# RHD2132_HS-accel-JAE.net
KiCad netlist of a schematic drawn in EAGLE
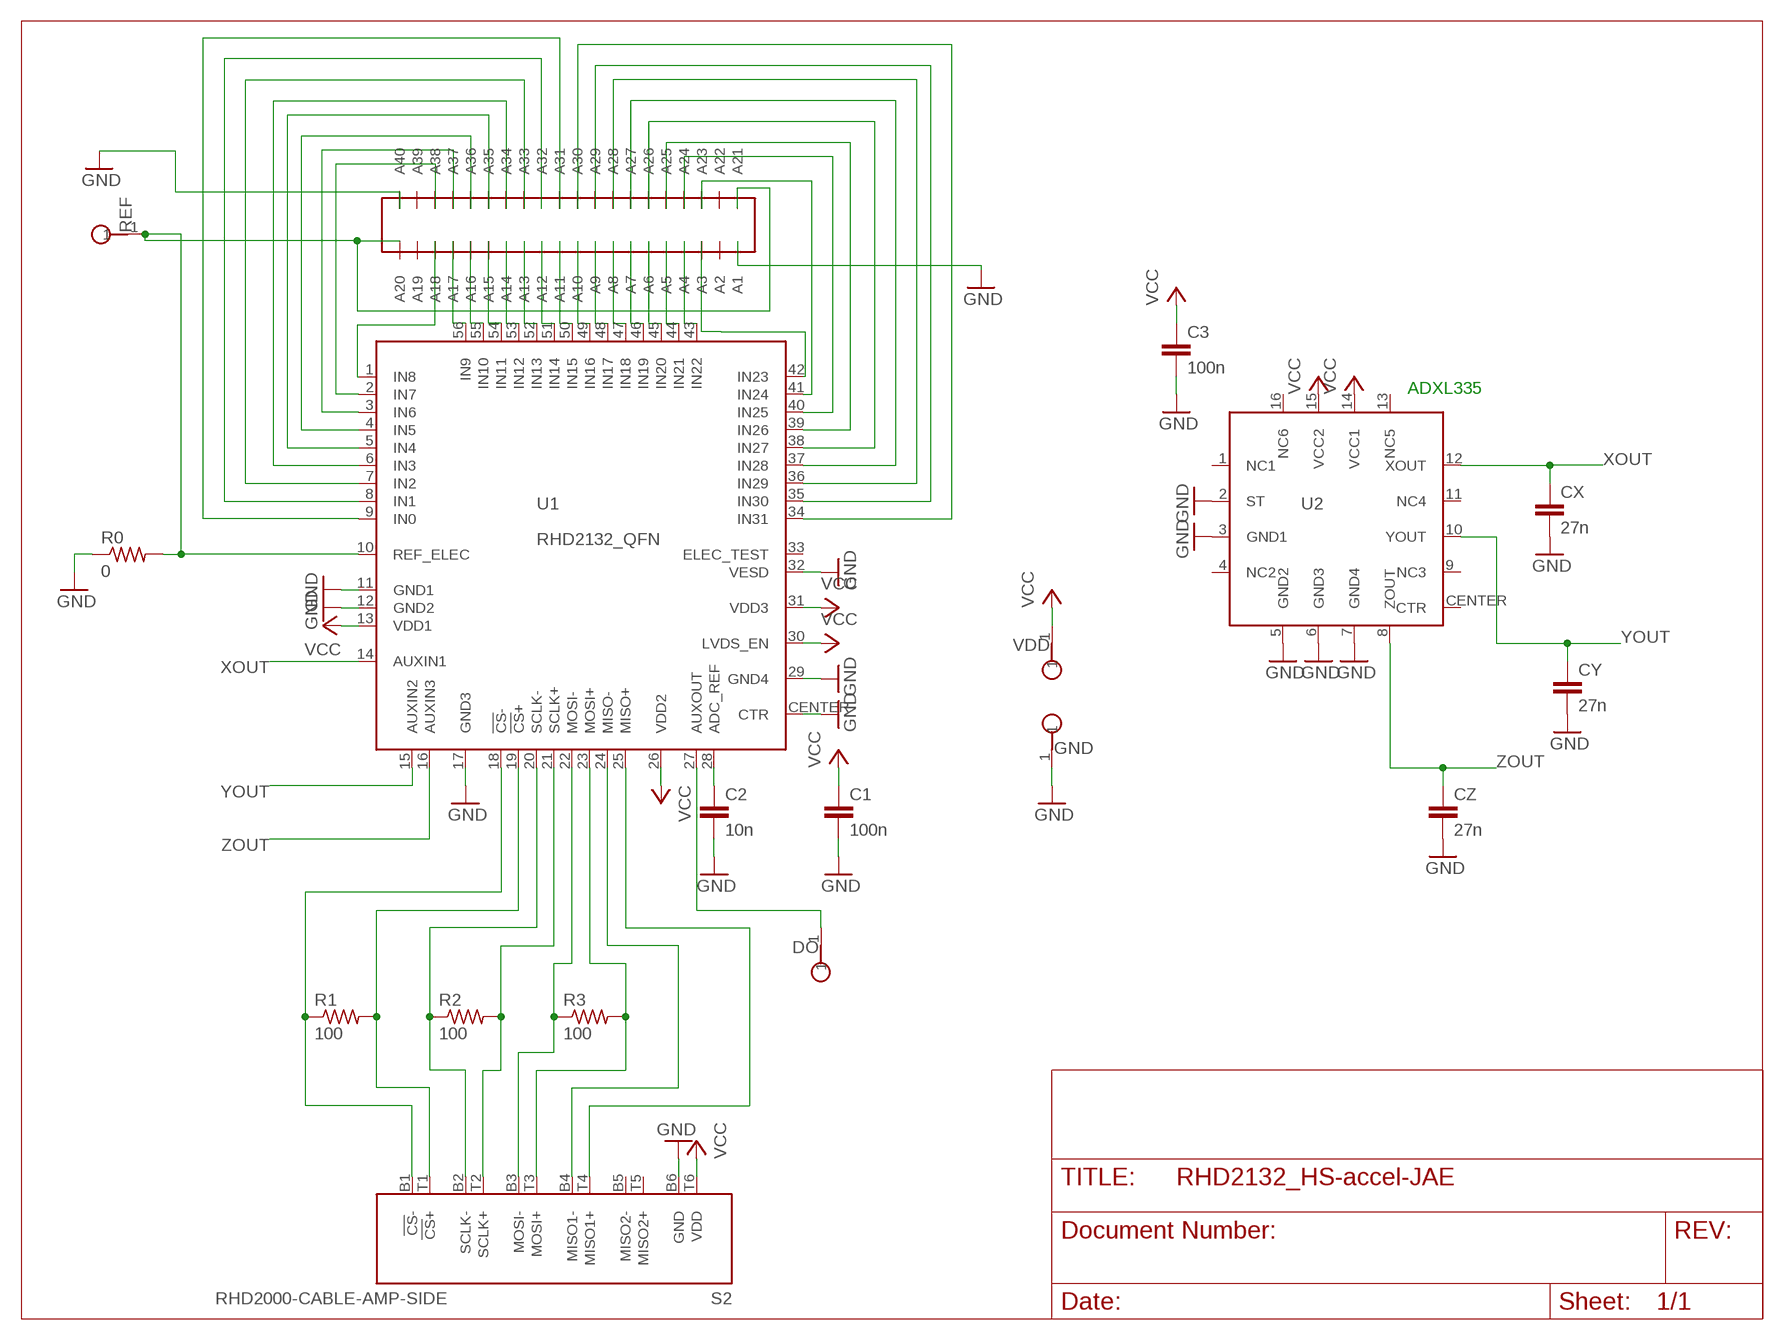
[diagram p0: schematic, sheet 1]

(export (version "E")
  (design (tool "Eeschema 10.0.6"))
  (components
    (comp (ref "C1")
      (value "100n")
      (footprint "eagle-import:0402")
      (libsource (lib "eagle-import") (part "C_0402"))
    )
    (comp (ref "C2")
      (value "10n")
      (footprint "eagle-import:0402")
      (libsource (lib "eagle-import") (part "C_0402"))
    )
    (comp (ref "C3")
      (value "100n")
      (footprint "eagle-import:0402")
      (libsource (lib "eagle-import") (part "C_0402"))
    )
    (comp (ref "CX")
      (value "27n")
      (footprint "eagle-import:0402")
      (libsource (lib "eagle-import") (part "C_0402"))
    )
    (comp (ref "CY")
      (value "27n")
      (footprint "eagle-import:0402")
      (libsource (lib "eagle-import") (part "C_0402"))
    )
    (comp (ref "CZ")
      (value "27n")
      (footprint "eagle-import:0402")
      (libsource (lib "eagle-import") (part "C_0402"))
    )
    (comp (ref "DO")
      (value "TESTPOINT_SMALL")
      (footprint "eagle-import:TESTPOINT_SMALL")
      (libsource (lib "eagle-import") (part "TESTPOINT_SMALL"))
    )
    (comp (ref "GND")
      (value "TESTPOINT_SMALL")
      (footprint "eagle-import:TESTPOINT_SMALL")
      (libsource (lib "eagle-import") (part "TESTPOINT_SMALL"))
    )
    (comp (ref "R0")
      (value "0")
      (footprint "eagle-import:0402")
      (libsource (lib "eagle-import") (part "R_0402"))
    )
    (comp (ref "R1")
      (value "100")
      (footprint "eagle-import:0402")
      (libsource (lib "eagle-import") (part "R_0402"))
    )
    (comp (ref "R2")
      (value "100")
      (footprint "eagle-import:0402")
      (libsource (lib "eagle-import") (part "R_0402"))
    )
    (comp (ref "R3")
      (value "100")
      (footprint "eagle-import:0402")
      (libsource (lib "eagle-import") (part "R_0402"))
    )
    (comp (ref "REF")
      (value "TESTPOINT_SMALL")
      (footprint "eagle-import:TESTPOINT_SMALL")
      (libsource (lib "eagle-import") (part "TESTPOINT_SMALL"))
    )
    (comp (ref "S2")
      (value "RHD2000-CABLE-AMP-SIDE")
      (footprint "eagle-import:OMNETICS_PZN-12-AA")
      (libsource (lib "eagle-import") (part "RHD2000-CABLE-AMP-SIDE"))
    )
    (comp (ref "U$1")
      (value "WR-40P-HFHD")
      (footprint "eagle-import:WR-40P-HFHD")
      (libsource (lib "eagle-import") (part "WR-40P-HFHD"))
    )
    (comp (ref "U1")
      (value "RHD2132_QFN")
      (footprint "eagle-import:QFN56_8_X_8_LARGE")
      (libsource (lib "eagle-import") (part "RHD2132_QFN"))
    )
    (comp (ref "U2")
      (value "ADXL335")
      (footprint "eagle-import:ADXL335")
      (libsource (lib "eagle-import") (part "ADXL335"))
    )
    (comp (ref "VDD")
      (value "TESTPOINT_SMALL")
      (footprint "eagle-import:TESTPOINT_SMALL")
      (libsource (lib "eagle-import") (part "TESTPOINT_SMALL"))
    )
  )
  (nets
    (net (code "1") (name "/XOUT") (class "Default")
      (node (ref "CX") (pin "1") (pinfunction "1_1") (pintype "passive"))
      (node (ref "U1") (pin "14") (pinfunction "AUXIN1_14") (pintype "input"))
      (node (ref "U2") (pin "12") (pinfunction "XOUT_12") (pintype "output"))
    )
    (net (code "2") (name "/YOUT") (class "Default")
      (node (ref "CY") (pin "1") (pinfunction "1_1") (pintype "passive"))
      (node (ref "U1") (pin "15") (pinfunction "AUXIN2_15") (pintype "input"))
      (node (ref "U2") (pin "10") (pinfunction "YOUT_10") (pintype "output"))
    )
    (net (code "3") (name "/ZOUT") (class "Default")
      (node (ref "CZ") (pin "1") (pinfunction "1_1") (pintype "passive"))
      (node (ref "U1") (pin "16") (pinfunction "AUXIN3_16") (pintype "input"))
      (node (ref "U2") (pin "8") (pinfunction "ZOUT_8") (pintype "output"))
    )
    (net (code "4") (name "GND") (class "Default")
      (node (ref "C1") (pin "2") (pinfunction "2_2") (pintype "passive"))
      (node (ref "C2") (pin "2") (pinfunction "2_2") (pintype "passive"))
      (node (ref "C3") (pin "2") (pinfunction "2_2") (pintype "passive"))
      (node (ref "CX") (pin "2") (pinfunction "2_2") (pintype "passive"))
      (node (ref "CY") (pin "2") (pinfunction "2_2") (pintype "passive"))
      (node (ref "CZ") (pin "2") (pinfunction "2_2") (pintype "passive"))
      (node (ref "GND") (pin "1") (pinfunction "1_1") (pintype "passive"))
      (node (ref "R0") (pin "1") (pinfunction "1_1") (pintype "passive"))
      (node (ref "S2") (pin "B6") (pinfunction "GND_B6") (pintype "power_in"))
      (node (ref "U$1") (pin "P$1") (pinfunction "A1_P$1") (pintype "bidirectional"))
      (node (ref "U$1") (pin "P$40") (pinfunction "A40_P$40") (pintype "bidirectional"))
      (node (ref "U1") (pin "11") (pinfunction "GND1_11") (pintype "power_in"))
      (node (ref "U1") (pin "12") (pinfunction "GND2_12") (pintype "power_in"))
      (node (ref "U1") (pin "17") (pinfunction "GND3_17") (pintype "power_in"))
      (node (ref "U1") (pin "29") (pinfunction "GND4_29") (pintype "power_in"))
      (node (ref "U1") (pin "32") (pinfunction "VESD_32") (pintype "power_in"))
      (node (ref "U1") (pin "CENTER") (pinfunction "CTR_CENTER") (pintype "power_in"))
      (node (ref "U2") (pin "2") (pinfunction "ST_2") (pintype "input"))
      (node (ref "U2") (pin "3") (pinfunction "GND1_3") (pintype "power_in"))
      (node (ref "U2") (pin "5") (pinfunction "GND2_5") (pintype "power_in"))
      (node (ref "U2") (pin "6") (pinfunction "GND3_6") (pintype "power_in"))
      (node (ref "U2") (pin "7") (pinfunction "GND4_7") (pintype "power_in"))
    )
    (net (code "5") (name "Net-(S2-MISO1+)") (class "Default")
      (node (ref "S2") (pin "T4") (pinfunction "MISO1+_T4") (pintype "bidirectional"))
      (node (ref "U1") (pin "25") (pinfunction "MISO+_25") (pintype "output"))
    )
    (net (code "6") (name "Net-(S2-MISO1-)") (class "Default")
      (node (ref "S2") (pin "B4") (pinfunction "MISO1-_B4") (pintype "bidirectional"))
      (node (ref "U1") (pin "24") (pinfunction "MISO-_24") (pintype "output"))
    )
    (net (code "7") (name "Net-(S2-MOSI+)") (class "Default")
      (node (ref "R3") (pin "2") (pinfunction "2_2") (pintype "passive"))
      (node (ref "S2") (pin "T3") (pinfunction "MOSI+_T3") (pintype "bidirectional"))
      (node (ref "U1") (pin "23") (pinfunction "MOSI+_23") (pintype "input"))
    )
    (net (code "8") (name "Net-(S2-MOSI-)") (class "Default")
      (node (ref "R3") (pin "1") (pinfunction "1_1") (pintype "passive"))
      (node (ref "S2") (pin "B3") (pinfunction "MOSI-_B3") (pintype "bidirectional"))
      (node (ref "U1") (pin "22") (pinfunction "MOSI-_22") (pintype "input"))
    )
    (net (code "9") (name "Net-(S2-SCLK+)") (class "Default")
      (node (ref "R2") (pin "2") (pinfunction "2_2") (pintype "passive"))
      (node (ref "S2") (pin "T2") (pinfunction "SCLK+_T2") (pintype "bidirectional"))
      (node (ref "U1") (pin "21") (pinfunction "SCLK+_21") (pintype "input"))
    )
    (net (code "10") (name "Net-(S2-SCLK-)") (class "Default")
      (node (ref "R2") (pin "1") (pinfunction "1_1") (pintype "passive"))
      (node (ref "S2") (pin "B2") (pinfunction "SCLK-_B2") (pintype "bidirectional"))
      (node (ref "U1") (pin "20") (pinfunction "SCLK-_20") (pintype "input"))
    )
    (net (code "11") (name "Net-(S2-~{CS}+)") (class "Default")
      (node (ref "R1") (pin "2") (pinfunction "2_2") (pintype "passive"))
      (node (ref "S2") (pin "T1") (pinfunction "~{CS}+_T1") (pintype "bidirectional"))
      (node (ref "U1") (pin "19") (pinfunction "~{CS}+_19") (pintype "input"))
    )
    (net (code "12") (name "Net-(S2-~{CS}-)") (class "Default")
      (node (ref "R1") (pin "1") (pinfunction "1_1") (pintype "passive"))
      (node (ref "S2") (pin "B1") (pinfunction "~{CS}-_B1") (pintype "bidirectional"))
      (node (ref "U1") (pin "18") (pinfunction "~{CS}-_18") (pintype "input"))
    )
    (net (code "13") (name "Net-(U$1-A3)") (class "Default")
      (node (ref "U$1") (pin "P$3") (pinfunction "A3_P$3") (pintype "bidirectional"))
      (node (ref "U1") (pin "42") (pinfunction "IN23_42") (pintype "input"))
    )
    (net (code "14") (name "Net-(U$1-A4)") (class "Default")
      (node (ref "U$1") (pin "P$4") (pinfunction "A4_P$4") (pintype "bidirectional"))
      (node (ref "U1") (pin "43") (pinfunction "IN22_43") (pintype "input"))
    )
    (net (code "15") (name "Net-(U$1-A5)") (class "Default")
      (node (ref "U$1") (pin "P$5") (pinfunction "A5_P$5") (pintype "bidirectional"))
      (node (ref "U1") (pin "44") (pinfunction "IN21_44") (pintype "input"))
    )
    (net (code "16") (name "Net-(U$1-A6)") (class "Default")
      (node (ref "U$1") (pin "P$6") (pinfunction "A6_P$6") (pintype "bidirectional"))
      (node (ref "U1") (pin "45") (pinfunction "IN20_45") (pintype "input"))
    )
    (net (code "17") (name "Net-(U$1-A7)") (class "Default")
      (node (ref "U$1") (pin "P$7") (pinfunction "A7_P$7") (pintype "bidirectional"))
      (node (ref "U1") (pin "46") (pinfunction "IN19_46") (pintype "input"))
    )
    (net (code "18") (name "Net-(U$1-A8)") (class "Default")
      (node (ref "U$1") (pin "P$8") (pinfunction "A8_P$8") (pintype "bidirectional"))
      (node (ref "U1") (pin "47") (pinfunction "IN18_47") (pintype "input"))
    )
    (net (code "19") (name "Net-(U$1-A9)") (class "Default")
      (node (ref "U$1") (pin "P$9") (pinfunction "A9_P$9") (pintype "bidirectional"))
      (node (ref "U1") (pin "48") (pinfunction "IN17_48") (pintype "input"))
    )
    (net (code "20") (name "Net-(U$1-A10)") (class "Default")
      (node (ref "U$1") (pin "P$10") (pinfunction "A10_P$10") (pintype "bidirectional"))
      (node (ref "U1") (pin "49") (pinfunction "IN16_49") (pintype "input"))
    )
    (net (code "21") (name "Net-(U$1-A11)") (class "Default")
      (node (ref "U$1") (pin "P$11") (pinfunction "A11_P$11") (pintype "bidirectional"))
      (node (ref "U1") (pin "50") (pinfunction "IN15_50") (pintype "input"))
    )
    (net (code "22") (name "Net-(U$1-A12)") (class "Default")
      (node (ref "U$1") (pin "P$12") (pinfunction "A12_P$12") (pintype "bidirectional"))
      (node (ref "U1") (pin "51") (pinfunction "IN14_51") (pintype "input"))
    )
    (net (code "23") (name "Net-(U$1-A13)") (class "Default")
      (node (ref "U$1") (pin "P$13") (pinfunction "A13_P$13") (pintype "bidirectional"))
      (node (ref "U1") (pin "52") (pinfunction "IN13_52") (pintype "input"))
    )
    (net (code "24") (name "Net-(U$1-A14)") (class "Default")
      (node (ref "U$1") (pin "P$14") (pinfunction "A14_P$14") (pintype "bidirectional"))
      (node (ref "U1") (pin "53") (pinfunction "IN12_53") (pintype "input"))
    )
    (net (code "25") (name "Net-(U$1-A15)") (class "Default")
      (node (ref "U$1") (pin "P$15") (pinfunction "A15_P$15") (pintype "bidirectional"))
      (node (ref "U1") (pin "54") (pinfunction "IN11_54") (pintype "input"))
    )
    (net (code "26") (name "Net-(U$1-A16)") (class "Default")
      (node (ref "U$1") (pin "P$16") (pinfunction "A16_P$16") (pintype "bidirectional"))
      (node (ref "U1") (pin "55") (pinfunction "IN10_55") (pintype "input"))
    )
    (net (code "27") (name "Net-(U$1-A17)") (class "Default")
      (node (ref "U$1") (pin "P$17") (pinfunction "A17_P$17") (pintype "bidirectional"))
      (node (ref "U1") (pin "56") (pinfunction "IN9_56") (pintype "input"))
    )
    (net (code "28") (name "Net-(U$1-A18)") (class "Default")
      (node (ref "U$1") (pin "P$18") (pinfunction "A18_P$18") (pintype "bidirectional"))
      (node (ref "U1") (pin "1") (pinfunction "IN8_1") (pintype "input"))
    )
    (net (code "29") (name "Net-(U$1-A20)") (class "Default")
      (node (ref "R0") (pin "2") (pinfunction "2_2") (pintype "passive"))
      (node (ref "REF") (pin "1") (pinfunction "1_1") (pintype "passive"))
      (node (ref "U$1") (pin "P$20") (pinfunction "A20_P$20") (pintype "bidirectional"))
      (node (ref "U1") (pin "10") (pinfunction "REF_ELEC_10") (pintype "input"))
    )
    (net (code "30") (name "Net-(U$1-A23)") (class "Default")
      (node (ref "U$1") (pin "P$23") (pinfunction "A23_P$23") (pintype "bidirectional"))
      (node (ref "U1") (pin "41") (pinfunction "IN24_41") (pintype "input"))
    )
    (net (code "31") (name "Net-(U$1-A24)") (class "Default")
      (node (ref "U$1") (pin "P$24") (pinfunction "A24_P$24") (pintype "bidirectional"))
      (node (ref "U1") (pin "40") (pinfunction "IN25_40") (pintype "input"))
    )
    (net (code "32") (name "Net-(U$1-A25)") (class "Default")
      (node (ref "U$1") (pin "P$25") (pinfunction "A25_P$25") (pintype "bidirectional"))
      (node (ref "U1") (pin "39") (pinfunction "IN26_39") (pintype "input"))
    )
    (net (code "33") (name "Net-(U$1-A26)") (class "Default")
      (node (ref "U$1") (pin "P$26") (pinfunction "A26_P$26") (pintype "bidirectional"))
      (node (ref "U1") (pin "38") (pinfunction "IN27_38") (pintype "input"))
    )
    (net (code "34") (name "Net-(U$1-A27)") (class "Default")
      (node (ref "U$1") (pin "P$27") (pinfunction "A27_P$27") (pintype "bidirectional"))
      (node (ref "U1") (pin "37") (pinfunction "IN28_37") (pintype "input"))
    )
    (net (code "35") (name "Net-(U$1-A28)") (class "Default")
      (node (ref "U$1") (pin "P$28") (pinfunction "A28_P$28") (pintype "bidirectional"))
      (node (ref "U1") (pin "36") (pinfunction "IN29_36") (pintype "input"))
    )
    (net (code "36") (name "Net-(U$1-A29)") (class "Default")
      (node (ref "U$1") (pin "P$29") (pinfunction "A29_P$29") (pintype "bidirectional"))
      (node (ref "U1") (pin "35") (pinfunction "IN30_35") (pintype "input"))
    )
    (net (code "37") (name "Net-(U$1-A30)") (class "Default")
      (node (ref "U$1") (pin "P$30") (pinfunction "A30_P$30") (pintype "bidirectional"))
      (node (ref "U1") (pin "34") (pinfunction "IN31_34") (pintype "input"))
    )
    (net (code "38") (name "Net-(U$1-A31)") (class "Default")
      (node (ref "U$1") (pin "P$31") (pinfunction "A31_P$31") (pintype "bidirectional"))
      (node (ref "U1") (pin "9") (pinfunction "IN0_9") (pintype "input"))
    )
    (net (code "39") (name "Net-(U$1-A32)") (class "Default")
      (node (ref "U$1") (pin "P$32") (pinfunction "A32_P$32") (pintype "bidirectional"))
      (node (ref "U1") (pin "8") (pinfunction "IN1_8") (pintype "input"))
    )
    (net (code "40") (name "Net-(U$1-A33)") (class "Default")
      (node (ref "U$1") (pin "P$33") (pinfunction "A33_P$33") (pintype "bidirectional"))
      (node (ref "U1") (pin "7") (pinfunction "IN2_7") (pintype "input"))
    )
    (net (code "41") (name "Net-(U$1-A34)") (class "Default")
      (node (ref "U$1") (pin "P$34") (pinfunction "A34_P$34") (pintype "bidirectional"))
      (node (ref "U1") (pin "6") (pinfunction "IN3_6") (pintype "input"))
    )
    (net (code "42") (name "Net-(U$1-A35)") (class "Default")
      (node (ref "U$1") (pin "P$35") (pinfunction "A35_P$35") (pintype "bidirectional"))
      (node (ref "U1") (pin "5") (pinfunction "IN4_5") (pintype "input"))
    )
    (net (code "43") (name "Net-(U$1-A36)") (class "Default")
      (node (ref "U$1") (pin "P$36") (pinfunction "A36_P$36") (pintype "bidirectional"))
      (node (ref "U1") (pin "4") (pinfunction "IN5_4") (pintype "input"))
    )
    (net (code "44") (name "Net-(U$1-A37)") (class "Default")
      (node (ref "U$1") (pin "P$37") (pinfunction "A37_P$37") (pintype "bidirectional"))
      (node (ref "U1") (pin "3") (pinfunction "IN6_3") (pintype "input"))
    )
    (net (code "45") (name "Net-(U$1-A38)") (class "Default")
      (node (ref "U$1") (pin "P$38") (pinfunction "A38_P$38") (pintype "bidirectional"))
      (node (ref "U1") (pin "2") (pinfunction "IN7_2") (pintype "input"))
    )
    (net (code "46") (name "Net-(U1-ADC_REF)") (class "Default")
      (node (ref "C2") (pin "1") (pinfunction "1_1") (pintype "passive"))
      (node (ref "U1") (pin "28") (pinfunction "ADC_REF_28") (pintype "passive"))
    )
    (net (code "47") (name "Net-(U1-AUXOUT)") (class "Default")
      (node (ref "DO") (pin "1") (pinfunction "1_1") (pintype "passive"))
      (node (ref "U1") (pin "27") (pinfunction "AUXOUT_27") (pintype "tri_state"))
    )
    (net (code "48") (name "VCC") (class "Default")
      (node (ref "C1") (pin "1") (pinfunction "1_1") (pintype "passive"))
      (node (ref "C3") (pin "1") (pinfunction "1_1") (pintype "passive"))
      (node (ref "S2") (pin "T6") (pinfunction "VDD_T6") (pintype "bidirectional"))
      (node (ref "U1") (pin "13") (pinfunction "VDD1_13") (pintype "power_in"))
      (node (ref "U1") (pin "26") (pinfunction "VDD2_26") (pintype "power_in"))
      (node (ref "U1") (pin "30") (pinfunction "LVDS_EN_30") (pintype "input"))
      (node (ref "U1") (pin "31") (pinfunction "VDD3_31") (pintype "power_in"))
      (node (ref "U2") (pin "14") (pinfunction "VCC1_14") (pintype "power_in"))
      (node (ref "U2") (pin "15") (pinfunction "VCC2_15") (pintype "power_in"))
      (node (ref "VDD") (pin "1") (pinfunction "1_1") (pintype "passive"))
    )
    (net (code "49") (name "unconnected-(S2-MISO2+-PadT5)") (class "Default")
      (node (ref "S2") (pin "T5") (pinfunction "MISO2+_T5") (pintype "bidirectional"))
    )
    (net (code "50") (name "unconnected-(S2-MISO2--PadB5)") (class "Default")
      (node (ref "S2") (pin "B5") (pinfunction "MISO2-_B5") (pintype "bidirectional"))
    )
    (net (code "51") (name "unconnected-(U$1-A2-PadP$2)") (class "Default")
      (node (ref "U$1") (pin "P$2") (pinfunction "A2_P$2") (pintype "bidirectional"))
    )
    (net (code "52") (name "unconnected-(U$1-A19-PadP$19)") (class "Default")
      (node (ref "U$1") (pin "P$19") (pinfunction "A19_P$19") (pintype "bidirectional"))
    )
    (net (code "53") (name "unconnected-(U$1-A21-PadP$21)") (class "Default")
      (node (ref "U$1") (pin "P$21") (pinfunction "A21_P$21") (pintype "bidirectional"))
    )
    (net (code "54") (name "unconnected-(U$1-A22-PadP$22)") (class "Default")
      (node (ref "U$1") (pin "P$22") (pinfunction "A22_P$22") (pintype "bidirectional"))
    )
    (net (code "55") (name "unconnected-(U$1-A39-PadP$39)") (class "Default")
      (node (ref "U$1") (pin "P$39") (pinfunction "A39_P$39") (pintype "bidirectional"))
    )
    (net (code "56") (name "unconnected-(U1-ELEC_TEST-Pad33)") (class "Default")
      (node (ref "U1") (pin "33") (pinfunction "ELEC_TEST_33") (pintype "input"))
    )
    (net (code "57") (name "unconnected-(U2-CTR-PadCENTER)") (class "Default")
      (node (ref "U2") (pin "CENTER") (pinfunction "CTR_CENTER") (pintype "passive"))
    )
    (net (code "58") (name "unconnected-(U2-NC1-Pad1)") (class "Default")
      (node (ref "U2") (pin "1") (pinfunction "NC1_1") (pintype "no_connect"))
    )
    (net (code "59") (name "unconnected-(U2-NC2-Pad4)") (class "Default")
      (node (ref "U2") (pin "4") (pinfunction "NC2_4") (pintype "no_connect"))
    )
    (net (code "60") (name "unconnected-(U2-NC3-Pad9)") (class "Default")
      (node (ref "U2") (pin "9") (pinfunction "NC3_9") (pintype "no_connect"))
    )
    (net (code "61") (name "unconnected-(U2-NC4-Pad11)") (class "Default")
      (node (ref "U2") (pin "11") (pinfunction "NC4_11") (pintype "no_connect"))
    )
    (net (code "62") (name "unconnected-(U2-NC5-Pad13)") (class "Default")
      (node (ref "U2") (pin "13") (pinfunction "NC5_13") (pintype "no_connect"))
    )
    (net (code "63") (name "unconnected-(U2-NC6-Pad16)") (class "Default")
      (node (ref "U2") (pin "16") (pinfunction "NC6_16") (pintype "no_connect"))
    )
  )
)
